# connector.net
KiCad netlist of a schematic drawn in Altium Designer
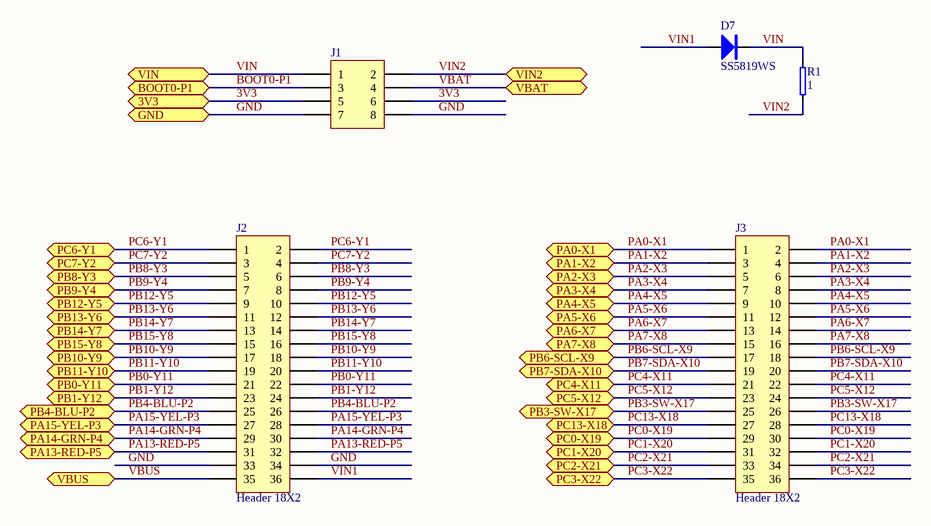
[diagram p0: connector.SchDoc]

(export (version "E")
  (design (tool "Eeschema 10.0.6"))
  (components
    (comp (ref "D7")
      (value "SS5819WS")
      (footprint "1N5819-SOD323")
      (libsource (lib "s_device") (part "Diode"))
    )
    (comp (ref "J1")
      (value "~")
      (footprint "HDR2X4")
      (description "Header, 4-Pin, Dual row")
      (fields (field (name "PUBLISHER") "Altium Limited"))
      (libsource (lib "Miscellaneous Connectors") (part "Header 4X2"))
    )
    (comp (ref "J2")
      (value "Header 18X2")
      (footprint "HDR2X18")
      (description "Header, 18-Pin, Dual row")
      (fields (field (name "PUBLISHER") "Altium Limited"))
      (libsource (lib "Miscellaneous Connectors") (part "Header 18X2"))
    )
    (comp (ref "J3")
      (value "Header 18X2")
      (footprint "HDR2X18")
      (description "Header, 18-Pin, Dual row")
      (fields (field (name "PUBLISHER") "Altium Limited"))
      (libsource (lib "Miscellaneous Connectors") (part "Header 18X2"))
    )
    (comp (ref "R1") (value "1") (footprint "SMD0402") (libsource (lib "s_device") (part "Res")))
  )
  (nets
    (net (code "1") (name "/3V3") (class "Default")
      (node (ref "J1") (pin "5") (pinfunction "5_5") (pintype "passive"))
      (node (ref "J1") (pin "6") (pinfunction "6_6") (pintype "passive"))
    )
    (net (code "2") (name "/BOOT0-P1") (class "Default")
      (node (ref "J1") (pin "3") (pinfunction "3_3") (pintype "passive"))
    )
    (net (code "3") (name "/GND") (class "Default")
      (node (ref "J1") (pin "7") (pinfunction "7_7") (pintype "passive"))
      (node (ref "J1") (pin "8") (pinfunction "8_8") (pintype "passive"))
      (node (ref "J2") (pin "33") (pinfunction "33_33") (pintype "passive"))
      (node (ref "J2") (pin "34") (pinfunction "34_34") (pintype "passive"))
    )
    (net (code "4") (name "/PA0-X1") (class "Default")
      (node (ref "J3") (pin "1") (pinfunction "1_1") (pintype "passive"))
      (node (ref "J3") (pin "2") (pinfunction "2_2") (pintype "passive"))
    )
    (net (code "5") (name "/PA1-X2") (class "Default")
      (node (ref "J3") (pin "3") (pinfunction "3_3") (pintype "passive"))
      (node (ref "J3") (pin "4") (pinfunction "4_4") (pintype "passive"))
    )
    (net (code "6") (name "/PA2-X3") (class "Default")
      (node (ref "J3") (pin "5") (pinfunction "5_5") (pintype "passive"))
      (node (ref "J3") (pin "6") (pinfunction "6_6") (pintype "passive"))
    )
    (net (code "7") (name "/PA3-X4") (class "Default")
      (node (ref "J3") (pin "7") (pinfunction "7_7") (pintype "passive"))
      (node (ref "J3") (pin "8") (pinfunction "8_8") (pintype "passive"))
    )
    (net (code "8") (name "/PA4-X5") (class "Default")
      (node (ref "J3") (pin "10") (pinfunction "10_10") (pintype "passive"))
      (node (ref "J3") (pin "9") (pinfunction "9_9") (pintype "passive"))
    )
    (net (code "9") (name "/PA5-X6") (class "Default")
      (node (ref "J3") (pin "11") (pinfunction "11_11") (pintype "passive"))
      (node (ref "J3") (pin "12") (pinfunction "12_12") (pintype "passive"))
    )
    (net (code "10") (name "/PA6-X7") (class "Default")
      (node (ref "J3") (pin "13") (pinfunction "13_13") (pintype "passive"))
      (node (ref "J3") (pin "14") (pinfunction "14_14") (pintype "passive"))
    )
    (net (code "11") (name "/PA7-X8") (class "Default")
      (node (ref "J3") (pin "15") (pinfunction "15_15") (pintype "passive"))
      (node (ref "J3") (pin "16") (pinfunction "16_16") (pintype "passive"))
    )
    (net (code "12") (name "/PA13-RED-P5") (class "Default")
      (node (ref "J2") (pin "31") (pinfunction "31_31") (pintype "passive"))
      (node (ref "J2") (pin "32") (pinfunction "32_32") (pintype "passive"))
    )
    (net (code "13") (name "/PA14-GRN-P4") (class "Default")
      (node (ref "J2") (pin "29") (pinfunction "29_29") (pintype "passive"))
      (node (ref "J2") (pin "30") (pinfunction "30_30") (pintype "passive"))
    )
    (net (code "14") (name "/PA15-YEL-P3") (class "Default")
      (node (ref "J2") (pin "27") (pinfunction "27_27") (pintype "passive"))
      (node (ref "J2") (pin "28") (pinfunction "28_28") (pintype "passive"))
    )
    (net (code "15") (name "/PB0-Y11") (class "Default")
      (node (ref "J2") (pin "21") (pinfunction "21_21") (pintype "passive"))
      (node (ref "J2") (pin "22") (pinfunction "22_22") (pintype "passive"))
    )
    (net (code "16") (name "/PB1-Y12") (class "Default")
      (node (ref "J2") (pin "23") (pinfunction "23_23") (pintype "passive"))
      (node (ref "J2") (pin "24") (pinfunction "24_24") (pintype "passive"))
    )
    (net (code "17") (name "/PB3-SW-X17") (class "Default")
      (node (ref "J3") (pin "25") (pinfunction "25_25") (pintype "passive"))
      (node (ref "J3") (pin "26") (pinfunction "26_26") (pintype "passive"))
    )
    (net (code "18") (name "/PB4-BLU-P2") (class "Default")
      (node (ref "J2") (pin "25") (pinfunction "25_25") (pintype "passive"))
      (node (ref "J2") (pin "26") (pinfunction "26_26") (pintype "passive"))
    )
    (net (code "19") (name "/PB6-SCL-X9") (class "Default")
      (node (ref "J3") (pin "17") (pinfunction "17_17") (pintype "passive"))
      (node (ref "J3") (pin "18") (pinfunction "18_18") (pintype "passive"))
    )
    (net (code "20") (name "/PB7-SDA-X10") (class "Default")
      (node (ref "J3") (pin "19") (pinfunction "19_19") (pintype "passive"))
      (node (ref "J3") (pin "20") (pinfunction "20_20") (pintype "passive"))
    )
    (net (code "21") (name "/PB8-Y3") (class "Default")
      (node (ref "J2") (pin "5") (pinfunction "5_5") (pintype "passive"))
      (node (ref "J2") (pin "6") (pinfunction "6_6") (pintype "passive"))
    )
    (net (code "22") (name "/PB9-Y4") (class "Default")
      (node (ref "J2") (pin "7") (pinfunction "7_7") (pintype "passive"))
      (node (ref "J2") (pin "8") (pinfunction "8_8") (pintype "passive"))
    )
    (net (code "23") (name "/PB10-Y9") (class "Default")
      (node (ref "J2") (pin "17") (pinfunction "17_17") (pintype "passive"))
      (node (ref "J2") (pin "18") (pinfunction "18_18") (pintype "passive"))
    )
    (net (code "24") (name "/PB11-Y10") (class "Default")
      (node (ref "J2") (pin "19") (pinfunction "19_19") (pintype "passive"))
      (node (ref "J2") (pin "20") (pinfunction "20_20") (pintype "passive"))
    )
    (net (code "25") (name "/PB12-Y5") (class "Default")
      (node (ref "J2") (pin "10") (pinfunction "10_10") (pintype "passive"))
      (node (ref "J2") (pin "9") (pinfunction "9_9") (pintype "passive"))
    )
    (net (code "26") (name "/PB13-Y6") (class "Default")
      (node (ref "J2") (pin "11") (pinfunction "11_11") (pintype "passive"))
      (node (ref "J2") (pin "12") (pinfunction "12_12") (pintype "passive"))
    )
    (net (code "27") (name "/PB14-Y7") (class "Default")
      (node (ref "J2") (pin "13") (pinfunction "13_13") (pintype "passive"))
      (node (ref "J2") (pin "14") (pinfunction "14_14") (pintype "passive"))
    )
    (net (code "28") (name "/PB15-Y8") (class "Default")
      (node (ref "J2") (pin "15") (pinfunction "15_15") (pintype "passive"))
      (node (ref "J2") (pin "16") (pinfunction "16_16") (pintype "passive"))
    )
    (net (code "29") (name "/PC0-X19") (class "Default")
      (node (ref "J3") (pin "29") (pinfunction "29_29") (pintype "passive"))
      (node (ref "J3") (pin "30") (pinfunction "30_30") (pintype "passive"))
    )
    (net (code "30") (name "/PC1-X20") (class "Default")
      (node (ref "J3") (pin "31") (pinfunction "31_31") (pintype "passive"))
      (node (ref "J3") (pin "32") (pinfunction "32_32") (pintype "passive"))
    )
    (net (code "31") (name "/PC2-X21") (class "Default")
      (node (ref "J3") (pin "33") (pinfunction "33_33") (pintype "passive"))
      (node (ref "J3") (pin "34") (pinfunction "34_34") (pintype "passive"))
    )
    (net (code "32") (name "/PC3-X22") (class "Default")
      (node (ref "J3") (pin "35") (pinfunction "35_35") (pintype "passive"))
      (node (ref "J3") (pin "36") (pinfunction "36_36") (pintype "passive"))
    )
    (net (code "33") (name "/PC4-X11") (class "Default")
      (node (ref "J3") (pin "21") (pinfunction "21_21") (pintype "passive"))
      (node (ref "J3") (pin "22") (pinfunction "22_22") (pintype "passive"))
    )
    (net (code "34") (name "/PC5-X12") (class "Default")
      (node (ref "J3") (pin "23") (pinfunction "23_23") (pintype "passive"))
      (node (ref "J3") (pin "24") (pinfunction "24_24") (pintype "passive"))
    )
    (net (code "35") (name "/PC6-Y1") (class "Default")
      (node (ref "J2") (pin "1") (pinfunction "1_1") (pintype "passive"))
      (node (ref "J2") (pin "2") (pinfunction "2_2") (pintype "passive"))
    )
    (net (code "36") (name "/PC7-Y2") (class "Default")
      (node (ref "J2") (pin "3") (pinfunction "3_3") (pintype "passive"))
      (node (ref "J2") (pin "4") (pinfunction "4_4") (pintype "passive"))
    )
    (net (code "37") (name "/PC13-X18") (class "Default")
      (node (ref "J3") (pin "27") (pinfunction "27_27") (pintype "passive"))
      (node (ref "J3") (pin "28") (pinfunction "28_28") (pintype "passive"))
    )
    (net (code "38") (name "/VBAT") (class "Default")
      (node (ref "J1") (pin "4") (pinfunction "4_4") (pintype "passive"))
    )
    (net (code "39") (name "/VBUS") (class "Default")
      (node (ref "J2") (pin "35") (pinfunction "35_35") (pintype "passive"))
    )
    (net (code "40") (name "/VIN") (class "Default")
      (node (ref "D7") (pin "2") (pintype "passive"))
      (node (ref "J1") (pin "1") (pinfunction "1_1") (pintype "passive"))
      (node (ref "R1") (pin "1") (pintype "passive"))
    )
    (net (code "41") (name "/VIN1") (class "Default")
      (node (ref "D7") (pin "1") (pintype "passive"))
      (node (ref "J2") (pin "36") (pinfunction "36_36") (pintype "passive"))
    )
    (net (code "42") (name "/VIN2") (class "Default")
      (node (ref "J1") (pin "2") (pinfunction "2_2") (pintype "passive"))
      (node (ref "R1") (pin "2") (pintype "passive"))
    )
  )
)
